# vc_board_v011.net
KiCad netlist of a schematic drawn in EAGLE
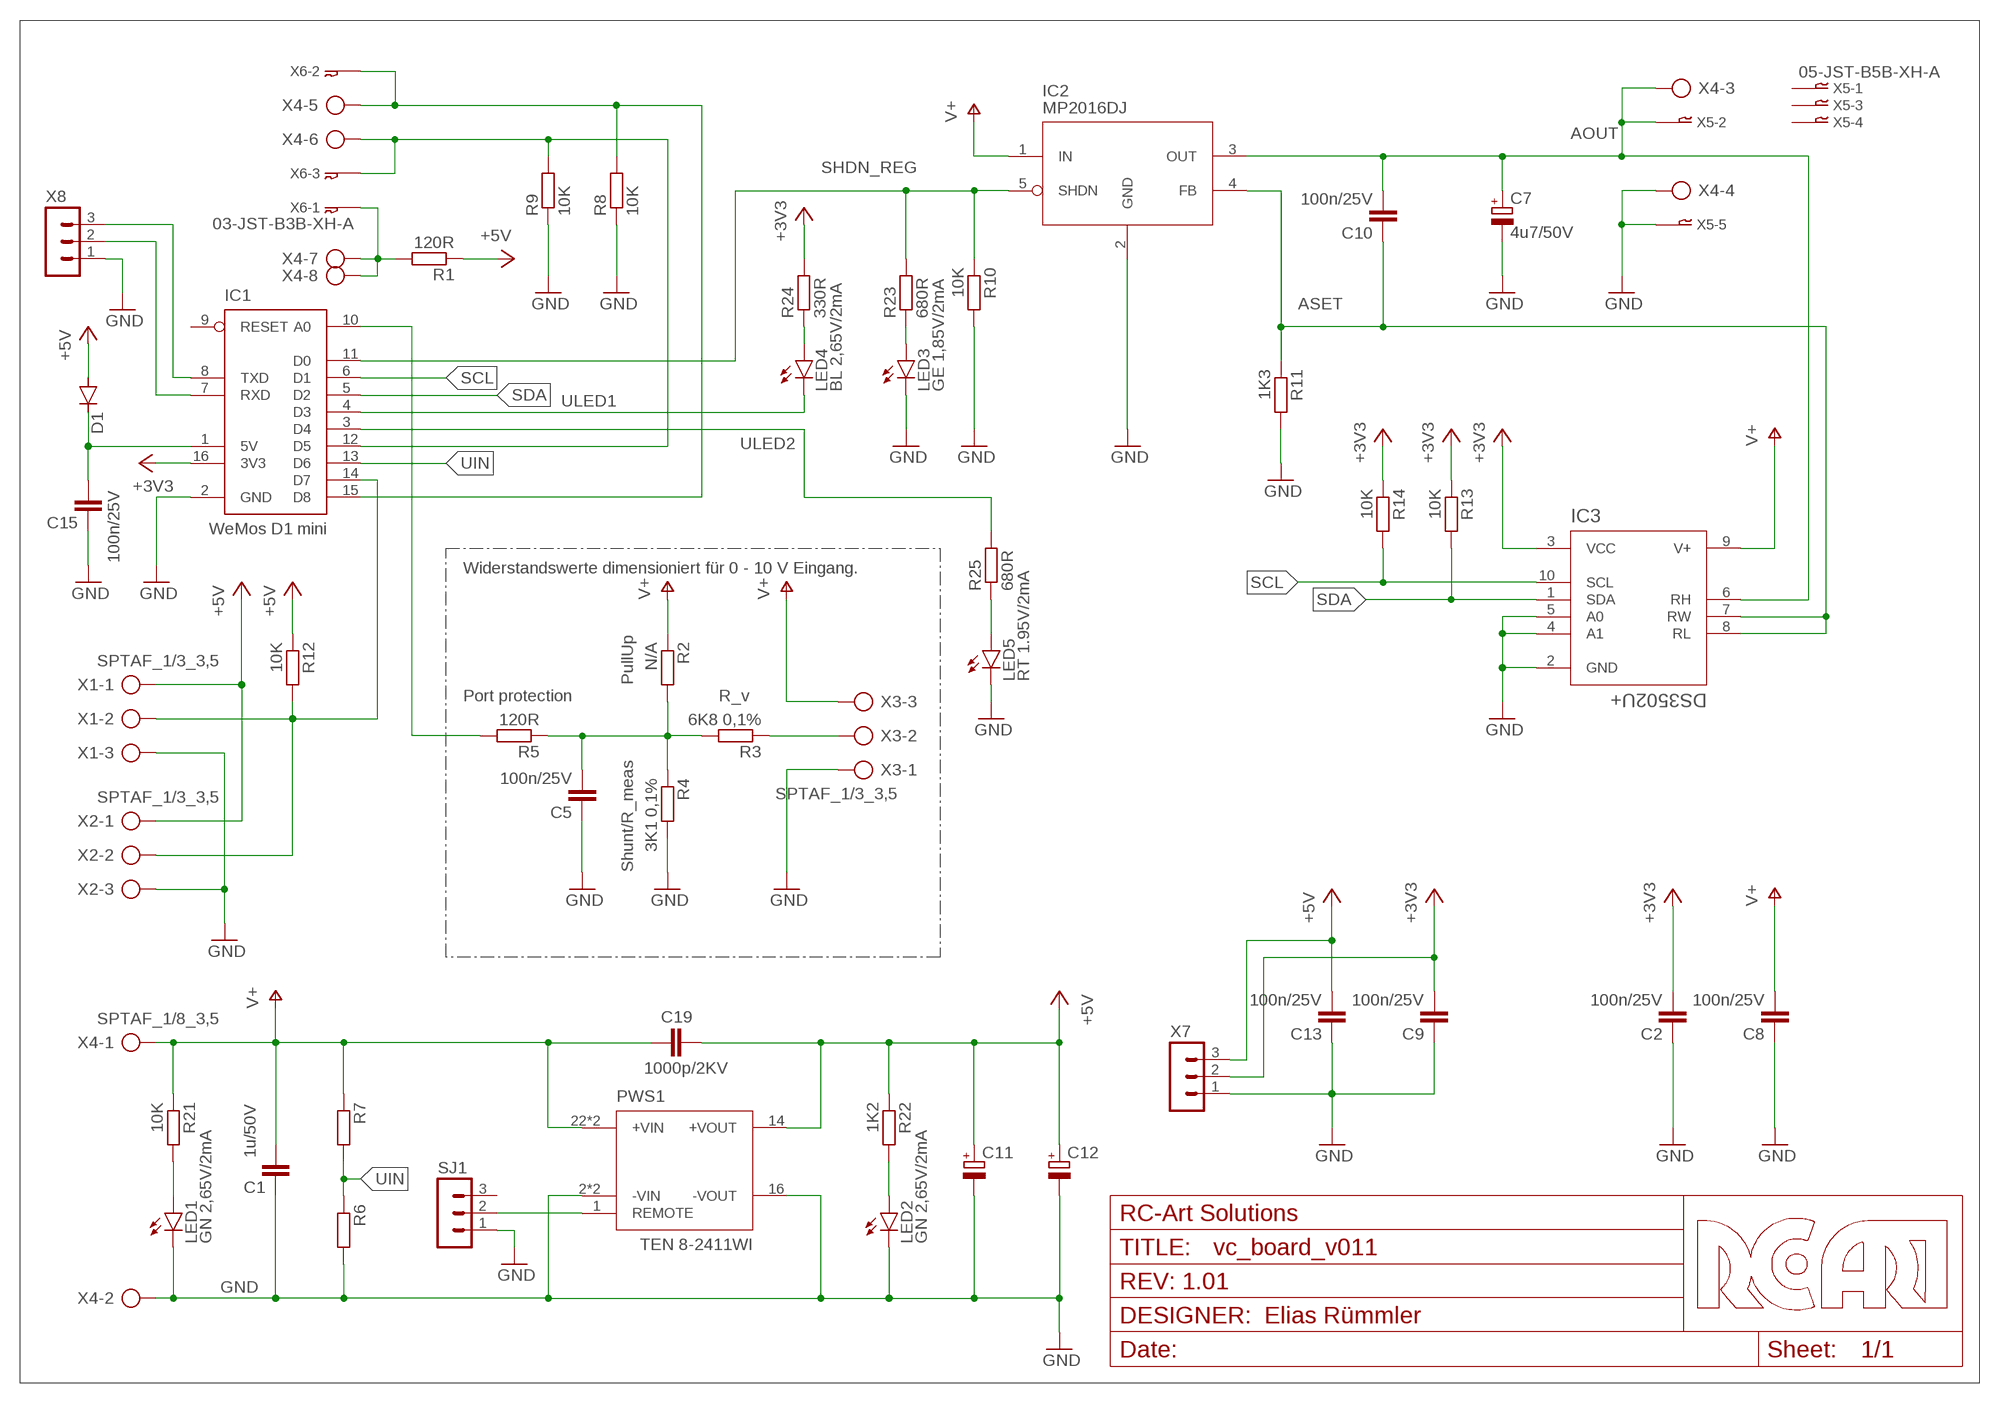
[diagram p0: schematic, sheet 1]

(export (version "E")
  (design (tool "Eeschema 10.0.6"))
  (components
    (comp (ref "C1")
      (value "1u/50V")
      (footprint "eagle-import:C1210K")
      (libsource (lib "eagle-import") (part "C-EUC1210K"))
    )
    (comp (ref "C2")
      (value "100n/25V")
      (footprint "eagle-import:C0805")
      (libsource (lib "eagle-import") (part "C-EUC0805"))
    )
    (comp (ref "C5")
      (value "100n/25V")
      (footprint "eagle-import:C0805")
      (libsource (lib "eagle-import") (part "C-EUC0805"))
    )
    (comp (ref "C7")
      (value "4u7/50V")
      (footprint "eagle-import:D_7343-31W")
      (libsource (lib "eagle-import") (part "CPOL-EUD/7343-31W"))
    )
    (comp (ref "C8")
      (value "100n/25V")
      (footprint "eagle-import:C0805")
      (libsource (lib "eagle-import") (part "C-EUC0805"))
    )
    (comp (ref "C9")
      (value "100n/25V")
      (footprint "eagle-import:C0805")
      (libsource (lib "eagle-import") (part "C-EUC0805"))
    )
    (comp (ref "C10")
      (value "100n/25V")
      (footprint "eagle-import:C0805")
      (libsource (lib "eagle-import") (part "C-EUC0805"))
    )
    (comp (ref "C11")
      (value "CPOL-EUD/7343-31W")
      (footprint "eagle-import:D_7343-31W")
      (libsource (lib "eagle-import") (part "CPOL-EUD/7343-31W"))
    )
    (comp (ref "C12")
      (value "CPOL-EUD/7343-31W")
      (footprint "eagle-import:D_7343-31W")
      (libsource (lib "eagle-import") (part "CPOL-EUD/7343-31W"))
    )
    (comp (ref "C13")
      (value "100n/25V")
      (footprint "eagle-import:C0805")
      (libsource (lib "eagle-import") (part "C-EUC0805"))
    )
    (comp (ref "C15")
      (value "100n/25V")
      (footprint "eagle-import:C0805")
      (libsource (lib "eagle-import") (part "C-EUC0805"))
    )
    (comp (ref "C19")
      (value "1000p/2KV")
      (footprint "eagle-import:C1206K")
      (libsource (lib "eagle-import") (part "C-EUC1206K"))
    )
    (comp (ref "D1")
      (value "DIODE-SMB")
      (footprint "eagle-import:SMB")
      (libsource (lib "eagle-import") (part "DIODE-SMB"))
    )
    (comp (ref "FRAME1")
      (value "MF_FRAMEDEFAULT")
      (footprint "eagle-import:MF_FRAME_DEFAULT")
      (fields
        (field (name "REVNUM") "REV: N/A")
        (field (name "DNAME") "N/A")
        (field (name "HOUSEPART") "0")
        (field (name "DNAME_1") "Elias Rümmler")
        (field (name "REVNUM_1") "REV: 1.01")
      )
      (libsource (lib "eagle-import") (part "MF_FRAMEDEFAULT"))
    )
    (comp (ref "IC1")
      (value "WeMos D1 mini")
      (footprint "eagle-import:D1_MINI")
      (libsource (lib "eagle-import") (part "D1_MINI"))
    )
    (comp (ref "IC2")
      (value "MP2016DJ")
      (footprint "eagle-import:TSOT23-5")
      (libsource (lib "eagle-import") (part "MP2016"))
    )
    (comp (ref "IC3")
      (value "DS3502U+")
      (footprint "eagle-import:21-0061L_MXM")
      (fields (field (name "MANUFACTURER_PART_NUMBER") "ds3502u+"))
      (libsource (lib "eagle-import") (part "DS3502U+"))
    )
    (comp (ref "LED1")
      (value "GN 2,65V/2mA")
      (footprint "eagle-import:CHIPLED_0805")
      (libsource (lib "eagle-import") (part "LEDCHIPLED_0805"))
    )
    (comp (ref "LED2")
      (value "GN 2,65V/2mA")
      (footprint "eagle-import:CHIPLED_0805")
      (libsource (lib "eagle-import") (part "LEDCHIPLED_0805"))
    )
    (comp (ref "LED3")
      (value "GE 1,85V/2mA")
      (footprint "eagle-import:CHIPLED_0805")
      (libsource (lib "eagle-import") (part "LEDCHIPLED_0805"))
    )
    (comp (ref "LED4")
      (value "BL 2,65V/2mA")
      (footprint "eagle-import:CHIPLED_0805")
      (libsource (lib "eagle-import") (part "LEDCHIPLED_0805"))
    )
    (comp (ref "LED5")
      (value "RT 1.95V/2mA")
      (footprint "eagle-import:CHIPLED_0805")
      (libsource (lib "eagle-import") (part "LEDCHIPLED_0805"))
    )
    (comp (ref "PWS1")
      (value "TEN 8-2411WI")
      (footprint "eagle-import:TEN8")
      (libsource (lib "eagle-import") (part "TEN8WI"))
    )
    (comp (ref "R1")
      (value "120R")
      (footprint "eagle-import:R0805")
      (libsource (lib "eagle-import") (part "R-EU_R0805"))
    )
    (comp (ref "R2")
      (value "N/A")
      (footprint "eagle-import:R0805")
      (libsource (lib "eagle-import") (part "R-EU_R0805"))
    )
    (comp (ref "R3")
      (value "6K8 0,1%")
      (footprint "eagle-import:R0805")
      (libsource (lib "eagle-import") (part "R-EU_R0805"))
    )
    (comp (ref "R4")
      (value "3K1 0,1%")
      (footprint "eagle-import:R0805")
      (libsource (lib "eagle-import") (part "R-EU_R0805"))
    )
    (comp (ref "R5")
      (value "120R")
      (footprint "eagle-import:R0805")
      (libsource (lib "eagle-import") (part "R-EU_R0805"))
    )
    (comp (ref "R6")
      (value "R-EU_R0805")
      (footprint "eagle-import:R0805")
      (libsource (lib "eagle-import") (part "R-EU_R0805"))
    )
    (comp (ref "R7")
      (value "R-EU_R0805")
      (footprint "eagle-import:R0805")
      (libsource (lib "eagle-import") (part "R-EU_R0805"))
    )
    (comp (ref "R8")
      (value "10K")
      (footprint "eagle-import:R0805")
      (libsource (lib "eagle-import") (part "R-EU_R0805"))
    )
    (comp (ref "R9")
      (value "10K")
      (footprint "eagle-import:R0805")
      (libsource (lib "eagle-import") (part "R-EU_R0805"))
    )
    (comp (ref "R10")
      (value "10K")
      (footprint "eagle-import:R0805")
      (libsource (lib "eagle-import") (part "R-EU_R0805"))
    )
    (comp (ref "R11")
      (value "1K3")
      (footprint "eagle-import:R0805")
      (libsource (lib "eagle-import") (part "R-EU_R0805"))
    )
    (comp (ref "R12")
      (value "10K")
      (footprint "eagle-import:R0805")
      (libsource (lib "eagle-import") (part "R-EU_R0805"))
    )
    (comp (ref "R13")
      (value "10K")
      (footprint "eagle-import:R0805")
      (libsource (lib "eagle-import") (part "R-EU_R0805"))
    )
    (comp (ref "R14")
      (value "10K")
      (footprint "eagle-import:R0805")
      (libsource (lib "eagle-import") (part "R-EU_R0805"))
    )
    (comp (ref "R21")
      (value "10K")
      (footprint "eagle-import:R0805")
      (libsource (lib "eagle-import") (part "R-EU_R0805"))
    )
    (comp (ref "R22")
      (value "1K2")
      (footprint "eagle-import:R0805")
      (libsource (lib "eagle-import") (part "R-EU_R0805"))
    )
    (comp (ref "R23")
      (value "680R")
      (footprint "eagle-import:R0805")
      (libsource (lib "eagle-import") (part "R-EU_R0805"))
    )
    (comp (ref "R24")
      (value "330R")
      (footprint "eagle-import:R0805")
      (libsource (lib "eagle-import") (part "R-EU_R0805"))
    )
    (comp (ref "R25")
      (value "680R")
      (footprint "eagle-import:R0805")
      (libsource (lib "eagle-import") (part "R-EU_R0805"))
    )
    (comp (ref "SJ1")
      (value "MA03-1")
      (footprint "eagle-import:MA03-1")
      (libsource (lib "eagle-import") (part "MA03-1"))
    )
    (comp (ref "X1")
      (value "SPTAF_1/3_3,5")
      (footprint "eagle-import:SPTAF_1_3_3,5")
      (libsource (lib "eagle-import") (part "SPTAF_1/3_3,5"))
    )
    (comp (ref "X2")
      (value "SPTAF_1/3_3,5")
      (footprint "eagle-import:SPTAF_1_3_3,5")
      (libsource (lib "eagle-import") (part "SPTAF_1/3_3,5"))
    )
    (comp (ref "X3")
      (value "SPTAF_1/3_3,5")
      (footprint "eagle-import:SPTAF_1_3_3,5")
      (libsource (lib "eagle-import") (part "SPTAF_1/3_3,5"))
    )
    (comp (ref "X4")
      (value "SPTAF_1/8_3,5")
      (footprint "eagle-import:SPTAF_1_8_3,5")
      (fields (field (name "MF") "FARNELL") (field (name "MPN") "1861991"))
      (libsource (lib "eagle-import") (part "SPTAF_1/8_3,5"))
    )
    (comp (ref "X5")
      (value "05-JST-B5B-XH-A")
      (footprint "eagle-import:B5B-XH")
      (libsource (lib "eagle-import") (part "05-JST-B5B-XH-A"))
    )
    (comp (ref "X6")
      (value "03-JST-B3B-XH-A")
      (footprint "eagle-import:B3B-XH")
      (libsource (lib "eagle-import") (part "03-JST-B3B-XH-A"))
    )
    (comp (ref "X7")
      (value "MA03-1")
      (footprint "eagle-import:MA03-1")
      (libsource (lib "eagle-import") (part "MA03-1"))
    )
    (comp (ref "X8")
      (value "MA03-1")
      (footprint "eagle-import:MA03-1")
      (libsource (lib "eagle-import") (part "MA03-1"))
    )
  )
  (nets
    (net (code "1") (name "+3V3") (class "Default")
      (node (ref "C2") (pin "2") (pinfunction "2_2") (pintype "passive"))
      (node (ref "C9") (pin "2") (pinfunction "2_2") (pintype "passive"))
      (node (ref "IC1") (pin "16") (pinfunction "3V3_16") (pintype "bidirectional"))
      (node (ref "IC3") (pin "3") (pinfunction "VCC_3") (pintype "power_in"))
      (node (ref "R13") (pin "1") (pinfunction "1_1") (pintype "passive"))
      (node (ref "R14") (pin "1") (pinfunction "1_1") (pintype "passive"))
      (node (ref "R24") (pin "2") (pinfunction "2_2") (pintype "passive"))
      (node (ref "X7") (pin "2") (pinfunction "2_2") (pintype "passive"))
    )
    (net (code "2") (name "+5V") (class "Default")
      (node (ref "C11") (pin "+") (pinfunction "+_+") (pintype "passive"))
      (node (ref "C12") (pin "+") (pinfunction "+_+") (pintype "passive"))
      (node (ref "C13") (pin "2") (pinfunction "2_2") (pintype "passive"))
      (node (ref "C19") (pin "2") (pinfunction "2_2") (pintype "passive"))
      (node (ref "D1") (pin "A") (pinfunction "A_A") (pintype "passive"))
      (node (ref "PWS1") (pin "14") (pinfunction "+VOUT_14") (pintype "bidirectional"))
      (node (ref "R1") (pin "1") (pinfunction "1_1") (pintype "passive"))
      (node (ref "R12") (pin "1") (pinfunction "1_1") (pintype "passive"))
      (node (ref "R22") (pin "1") (pinfunction "1_1") (pintype "passive"))
      (node (ref "X1") (pin "1") (pinfunction "KL_1") (pintype "passive"))
      (node (ref "X1") (pin "1A") (pinfunction "KL_1A") (pintype "passive"))
      (node (ref "X2") (pin "1") (pinfunction "KL_1") (pintype "passive"))
      (node (ref "X2") (pin "1A") (pinfunction "KL_1A") (pintype "passive"))
      (node (ref "X7") (pin "3") (pinfunction "3_3") (pintype "passive"))
    )
    (net (code "3") (name "/AOUT") (class "Default")
      (node (ref "C10") (pin "2") (pinfunction "2_2") (pintype "passive"))
      (node (ref "C7") (pin "+") (pinfunction "+_+") (pintype "passive"))
      (node (ref "IC2") (pin "3") (pinfunction "OUT_3") (pintype "output"))
      (node (ref "IC3") (pin "6") (pinfunction "RH_6") (pintype "passive"))
      (node (ref "X4") (pin "3") (pinfunction "KL_3") (pintype "passive"))
      (node (ref "X4") (pin "3A") (pinfunction "KL_3A") (pintype "passive"))
      (node (ref "X5") (pin "P$2") (pinfunction "1_P$2") (pintype "passive"))
    )
    (net (code "4") (name "/ASET") (class "Default")
      (node (ref "C10") (pin "1") (pinfunction "1_1") (pintype "passive"))
      (node (ref "IC2") (pin "4") (pinfunction "FB_4") (pintype "bidirectional"))
      (node (ref "IC3") (pin "7") (pinfunction "RW_7") (pintype "passive"))
      (node (ref "IC3") (pin "8") (pinfunction "RL_8") (pintype "passive"))
      (node (ref "R11") (pin "1") (pinfunction "1_1") (pintype "passive"))
    )
    (net (code "5") (name "/SHDN_REG") (class "Default")
      (node (ref "IC1") (pin "11") (pinfunction "D0_11") (pintype "bidirectional"))
      (node (ref "IC2") (pin "5") (pinfunction "SHDN_5") (pintype "bidirectional"))
      (node (ref "R10") (pin "1") (pinfunction "1_1") (pintype "passive"))
      (node (ref "R23") (pin "2") (pinfunction "2_2") (pintype "passive"))
    )
    (net (code "6") (name "/ULED1") (class "Default")
      (node (ref "IC1") (pin "4") (pinfunction "D3_4") (pintype "bidirectional"))
      (node (ref "LED4") (pin "C") (pinfunction "C_C") (pintype "passive"))
    )
    (net (code "7") (name "/ULED2") (class "Default")
      (node (ref "IC1") (pin "3") (pinfunction "D4_3") (pintype "bidirectional"))
      (node (ref "R25") (pin "2") (pinfunction "2_2") (pintype "passive"))
    )
    (net (code "8") (name "GND") (class "Default")
      (node (ref "C1") (pin "1") (pinfunction "1_1") (pintype "passive"))
      (node (ref "C11") (pin "-") (pinfunction "-_-") (pintype "passive"))
      (node (ref "C12") (pin "-") (pinfunction "-_-") (pintype "passive"))
      (node (ref "C13") (pin "1") (pinfunction "1_1") (pintype "passive"))
      (node (ref "C15") (pin "1") (pinfunction "1_1") (pintype "passive"))
      (node (ref "C2") (pin "1") (pinfunction "1_1") (pintype "passive"))
      (node (ref "C5") (pin "1") (pinfunction "1_1") (pintype "passive"))
      (node (ref "C7") (pin "-") (pinfunction "-_-") (pintype "passive"))
      (node (ref "C8") (pin "1") (pinfunction "1_1") (pintype "passive"))
      (node (ref "C9") (pin "1") (pinfunction "1_1") (pintype "passive"))
      (node (ref "IC1") (pin "2") (pinfunction "GND_2") (pintype "bidirectional"))
      (node (ref "IC2") (pin "2") (pinfunction "GND_2") (pintype "power_in"))
      (node (ref "IC3") (pin "2") (pinfunction "GND_2") (pintype "power_in"))
      (node (ref "IC3") (pin "4") (pinfunction "A1_4") (pintype "input"))
      (node (ref "IC3") (pin "5") (pinfunction "A0_5") (pintype "input"))
      (node (ref "LED1") (pin "C") (pinfunction "C_C") (pintype "passive"))
      (node (ref "LED2") (pin "C") (pinfunction "C_C") (pintype "passive"))
      (node (ref "LED3") (pin "C") (pinfunction "C_C") (pintype "passive"))
      (node (ref "LED5") (pin "C") (pinfunction "C_C") (pintype "passive"))
      (node (ref "PWS1") (pin "16") (pinfunction "-VOUT_16") (pintype "bidirectional"))
      (node (ref "PWS1") (pin "2") (pinfunction "-VIN_2") (pintype "bidirectional"))
      (node (ref "PWS1") (pin "3") (pinfunction "-VIN_3") (pintype "bidirectional"))
      (node (ref "R10") (pin "2") (pinfunction "2_2") (pintype "passive"))
      (node (ref "R11") (pin "2") (pinfunction "2_2") (pintype "passive"))
      (node (ref "R4") (pin "2") (pinfunction "2_2") (pintype "passive"))
      (node (ref "R6") (pin "2") (pinfunction "2_2") (pintype "passive"))
      (node (ref "R8") (pin "1") (pinfunction "1_1") (pintype "passive"))
      (node (ref "R9") (pin "1") (pinfunction "1_1") (pintype "passive"))
      (node (ref "SJ1") (pin "1") (pinfunction "1_1") (pintype "passive"))
      (node (ref "X1") (pin "3") (pinfunction "KL_3") (pintype "passive"))
      (node (ref "X1") (pin "3A") (pinfunction "KL_3A") (pintype "passive"))
      (node (ref "X2") (pin "3") (pinfunction "KL_3") (pintype "passive"))
      (node (ref "X2") (pin "3A") (pinfunction "KL_3A") (pintype "passive"))
      (node (ref "X3") (pin "1") (pinfunction "KL_1") (pintype "passive"))
      (node (ref "X3") (pin "1A") (pinfunction "KL_1A") (pintype "passive"))
      (node (ref "X4") (pin "2") (pinfunction "KL_2") (pintype "passive"))
      (node (ref "X4") (pin "2A") (pinfunction "KL_2A") (pintype "passive"))
      (node (ref "X4") (pin "4") (pinfunction "KL_4") (pintype "passive"))
      (node (ref "X4") (pin "4A") (pinfunction "KL_4A") (pintype "passive"))
      (node (ref "X5") (pin "P$5") (pinfunction "1_P$5") (pintype "passive"))
      (node (ref "X7") (pin "1") (pinfunction "1_1") (pintype "passive"))
      (node (ref "X8") (pin "1") (pinfunction "1_1") (pintype "passive"))
    )
    (net (code "9") (name "Net-(C5-Pad2)") (class "Default")
      (node (ref "C5") (pin "2") (pinfunction "2_2") (pintype "passive"))
      (node (ref "R2") (pin "2") (pinfunction "2_2") (pintype "passive"))
      (node (ref "R3") (pin "2") (pinfunction "2_2") (pintype "passive"))
      (node (ref "R4") (pin "1") (pinfunction "1_1") (pintype "passive"))
      (node (ref "R5") (pin "1") (pinfunction "1_1") (pintype "passive"))
    )
    (net (code "10") (name "Net-(IC1-5V)") (class "Default")
      (node (ref "C15") (pin "2") (pinfunction "2_2") (pintype "passive"))
      (node (ref "D1") (pin "C") (pinfunction "C_C") (pintype "passive"))
      (node (ref "IC1") (pin "1") (pinfunction "5V_1") (pintype "bidirectional"))
    )
    (net (code "11") (name "Net-(IC1-A0)") (class "Default")
      (node (ref "IC1") (pin "10") (pinfunction "A0_10") (pintype "bidirectional"))
      (node (ref "R5") (pin "2") (pinfunction "2_2") (pintype "passive"))
    )
    (net (code "12") (name "Net-(IC1-D5)") (class "Default")
      (node (ref "IC1") (pin "12") (pinfunction "D5_12") (pintype "bidirectional"))
      (node (ref "R9") (pin "2") (pinfunction "2_2") (pintype "passive"))
      (node (ref "X4") (pin "6") (pinfunction "KL_6") (pintype "passive"))
      (node (ref "X4") (pin "6A") (pinfunction "KL_6A") (pintype "passive"))
      (node (ref "X6") (pin "P$3") (pinfunction "1_P$3") (pintype "passive"))
    )
    (net (code "13") (name "Net-(IC1-D7)") (class "Default")
      (node (ref "IC1") (pin "14") (pinfunction "D7_14") (pintype "bidirectional"))
      (node (ref "R12") (pin "2") (pinfunction "2_2") (pintype "passive"))
      (node (ref "X1") (pin "2") (pinfunction "KL_2") (pintype "passive"))
      (node (ref "X1") (pin "2A") (pinfunction "KL_2A") (pintype "passive"))
      (node (ref "X2") (pin "2") (pinfunction "KL_2") (pintype "passive"))
      (node (ref "X2") (pin "2A") (pinfunction "KL_2A") (pintype "passive"))
    )
    (net (code "14") (name "Net-(IC1-D8)") (class "Default")
      (node (ref "IC1") (pin "15") (pinfunction "D8_15") (pintype "bidirectional"))
      (node (ref "R8") (pin "2") (pinfunction "2_2") (pintype "passive"))
      (node (ref "X4") (pin "5") (pinfunction "KL_5") (pintype "passive"))
      (node (ref "X4") (pin "5A") (pinfunction "KL_5A") (pintype "passive"))
      (node (ref "X6") (pin "P$2") (pinfunction "1_P$2") (pintype "passive"))
    )
    (net (code "15") (name "Net-(IC1-RXD)") (class "Default")
      (node (ref "IC1") (pin "7") (pinfunction "RXD_7") (pintype "bidirectional"))
      (node (ref "X8") (pin "2") (pinfunction "2_2") (pintype "passive"))
    )
    (net (code "16") (name "Net-(IC1-TXD)") (class "Default")
      (node (ref "IC1") (pin "8") (pinfunction "TXD_8") (pintype "bidirectional"))
      (node (ref "X8") (pin "3") (pinfunction "3_3") (pintype "passive"))
    )
    (net (code "17") (name "Net-(LED1-PadA)") (class "Default")
      (node (ref "LED1") (pin "A") (pinfunction "A_A") (pintype "passive"))
      (node (ref "R21") (pin "2") (pinfunction "2_2") (pintype "passive"))
    )
    (net (code "18") (name "Net-(LED2-PadA)") (class "Default")
      (node (ref "LED2") (pin "A") (pinfunction "A_A") (pintype "passive"))
      (node (ref "R22") (pin "2") (pinfunction "2_2") (pintype "passive"))
    )
    (net (code "19") (name "Net-(LED3-PadA)") (class "Default")
      (node (ref "LED3") (pin "A") (pinfunction "A_A") (pintype "passive"))
      (node (ref "R23") (pin "1") (pinfunction "1_1") (pintype "passive"))
    )
    (net (code "20") (name "Net-(LED4-PadA)") (class "Default")
      (node (ref "LED4") (pin "A") (pinfunction "A_A") (pintype "passive"))
      (node (ref "R24") (pin "1") (pinfunction "1_1") (pintype "passive"))
    )
    (net (code "21") (name "Net-(LED5-PadA)") (class "Default")
      (node (ref "LED5") (pin "A") (pinfunction "A_A") (pintype "passive"))
      (node (ref "R25") (pin "1") (pinfunction "1_1") (pintype "passive"))
    )
    (net (code "22") (name "Net-(PWS1-REMOTE)") (class "Default")
      (node (ref "PWS1") (pin "1") (pinfunction "REMOTE_1") (pintype "bidirectional"))
      (node (ref "SJ1") (pin "2") (pinfunction "2_2") (pintype "passive"))
    )
    (net (code "23") (name "Net-(R3-Pad1)") (class "Default")
      (node (ref "R3") (pin "1") (pinfunction "1_1") (pintype "passive"))
      (node (ref "X3") (pin "2") (pinfunction "KL_2") (pintype "passive"))
      (node (ref "X3") (pin "2A") (pinfunction "KL_2A") (pintype "passive"))
    )
    (net (code "24") (name "Net-(X6A-1)") (class "Default")
      (node (ref "R1") (pin "2") (pinfunction "2_2") (pintype "passive"))
      (node (ref "X4") (pin "7") (pinfunction "KL_7") (pintype "passive"))
      (node (ref "X4") (pin "7A") (pinfunction "KL_7A") (pintype "passive"))
      (node (ref "X4") (pin "8") (pinfunction "KL_8") (pintype "passive"))
      (node (ref "X4") (pin "8A") (pinfunction "KL_8A") (pintype "passive"))
      (node (ref "X6") (pin "P$1") (pinfunction "1_P$1") (pintype "passive"))
    )
    (net (code "25") (name "SCL") (class "Default")
      (node (ref "IC1") (pin "6") (pinfunction "D1_6") (pintype "bidirectional"))
      (node (ref "IC3") (pin "10") (pinfunction "SCL_10") (pintype "input"))
      (node (ref "R14") (pin "2") (pinfunction "2_2") (pintype "passive"))
    )
    (net (code "26") (name "SDA") (class "Default")
      (node (ref "IC1") (pin "5") (pinfunction "D2_5") (pintype "bidirectional"))
      (node (ref "IC3") (pin "1") (pinfunction "SDA_1") (pintype "bidirectional"))
      (node (ref "R13") (pin "2") (pinfunction "2_2") (pintype "passive"))
    )
    (net (code "27") (name "UIN") (class "Default")
      (node (ref "IC1") (pin "13") (pinfunction "D6_13") (pintype "bidirectional"))
      (node (ref "R6") (pin "1") (pinfunction "1_1") (pintype "passive"))
      (node (ref "R7") (pin "2") (pinfunction "2_2") (pintype "passive"))
    )
    (net (code "28") (name "V+") (class "Default")
      (node (ref "C1") (pin "2") (pinfunction "2_2") (pintype "passive"))
      (node (ref "C19") (pin "1") (pinfunction "1_1") (pintype "passive"))
      (node (ref "C8") (pin "2") (pinfunction "2_2") (pintype "passive"))
      (node (ref "IC2") (pin "1") (pinfunction "IN_1") (pintype "input"))
      (node (ref "IC3") (pin "9") (pinfunction "V+_9") (pintype "power_in"))
      (node (ref "PWS1") (pin "22") (pinfunction "+VIN_22") (pintype "bidirectional"))
      (node (ref "PWS1") (pin "23") (pinfunction "+VIN_23") (pintype "bidirectional"))
      (node (ref "R2") (pin "1") (pinfunction "1_1") (pintype "passive"))
      (node (ref "R21") (pin "1") (pinfunction "1_1") (pintype "passive"))
      (node (ref "R7") (pin "1") (pinfunction "1_1") (pintype "passive"))
      (node (ref "X3") (pin "3") (pinfunction "KL_3") (pintype "passive"))
      (node (ref "X3") (pin "3A") (pinfunction "KL_3A") (pintype "passive"))
      (node (ref "X4") (pin "1") (pinfunction "KL_1") (pintype "passive"))
      (node (ref "X4") (pin "1A") (pinfunction "KL_1A") (pintype "passive"))
    )
    (net (code "29") (name "unconnected-(IC1-RESET-Pad9)") (class "Default")
      (node (ref "IC1") (pin "9") (pinfunction "RESET_9") (pintype "bidirectional"))
    )
    (net (code "30") (name "unconnected-(SJ1-Pad3)") (class "Default")
      (node (ref "SJ1") (pin "3") (pinfunction "3_3") (pintype "passive"))
    )
    (net (code "31") (name "unconnected-(X5A-1-PadP$1)") (class "Default")
      (node (ref "X5") (pin "P$1") (pinfunction "1_P$1") (pintype "passive"))
    )
    (net (code "32") (name "unconnected-(X5C-1-PadP$3)") (class "Default")
      (node (ref "X5") (pin "P$3") (pinfunction "1_P$3") (pintype "passive"))
    )
    (net (code "33") (name "unconnected-(X5D-1-PadP$4)") (class "Default")
      (node (ref "X5") (pin "P$4") (pinfunction "1_P$4") (pintype "passive"))
    )
  )
)
